# Peripherals.net
KiCad netlist of a schematic drawn in Altium Designer
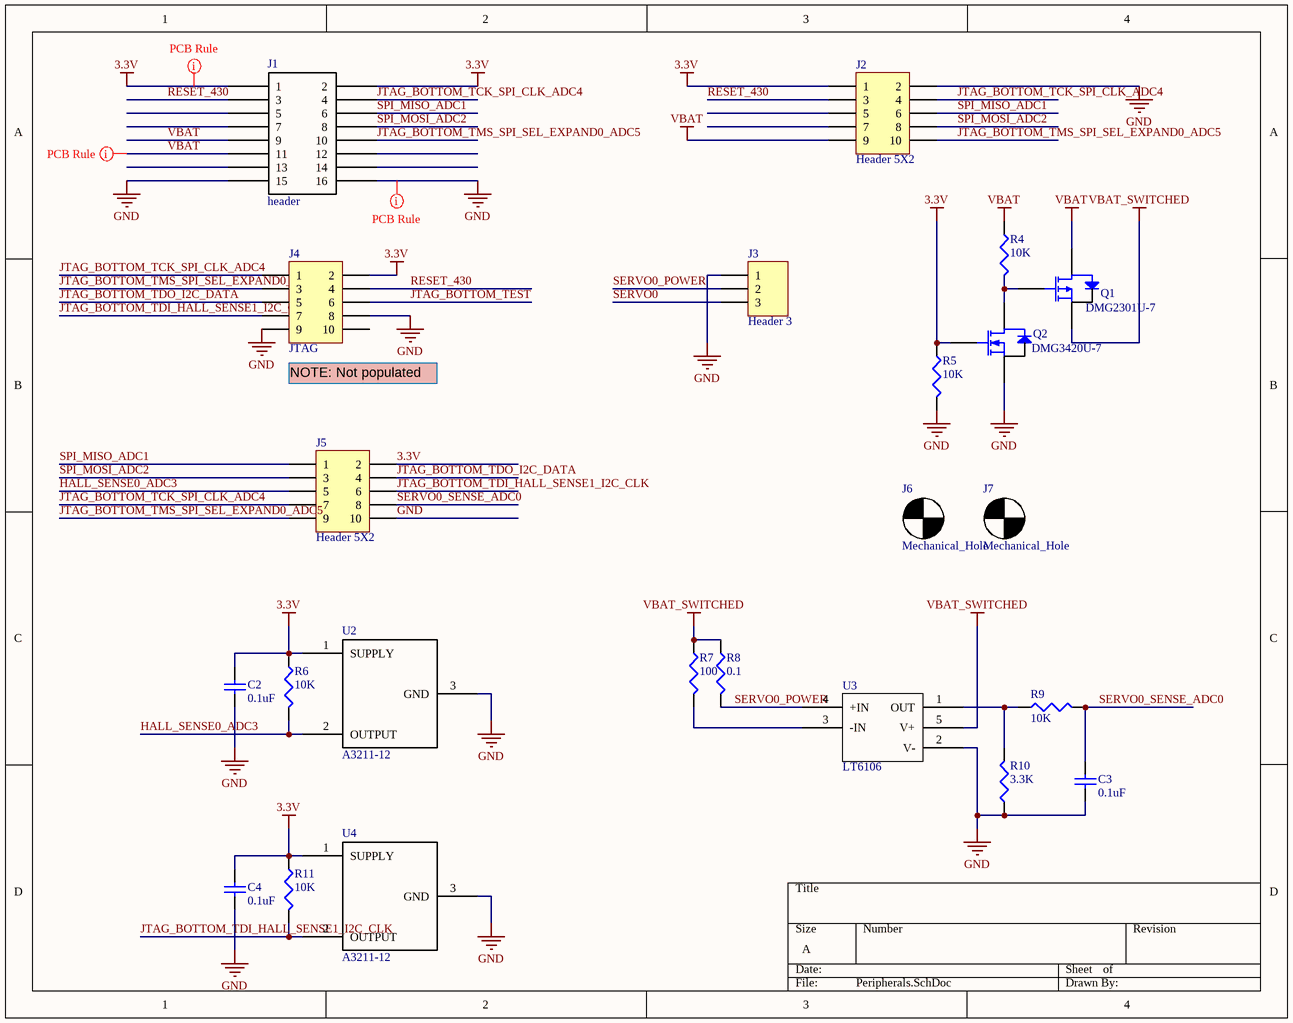
[diagram p0: Peripherals.SchDoc]

(export (version "E")
  (design (tool "Eeschema 10.0.6"))
  (components
    (comp (ref "C2")
      (value "0.1uF")
      (footprint "CAPC1005L")
      (description "Capacitor (Semiconductor SIM Model)")
      (fields (field (name "Comment") "Cap Semi") (field (name "PUBLISHER") "Altium Limited"))
      (libsource (lib "Miscellaneous Devices") (part "Cap Semi"))
    )
    (comp (ref "C3")
      (value "0.1uF")
      (footprint "CAPC1005L")
      (description "Capacitor (Semiconductor SIM Model)")
      (fields (field (name "Comment") "Cap Semi") (field (name "PUBLISHER") "Altium Limited"))
      (libsource (lib "Miscellaneous Devices") (part "Cap Semi"))
    )
    (comp (ref "C4")
      (value "0.1uF")
      (footprint "CAPC1005L")
      (description "Capacitor (Semiconductor SIM Model)")
      (fields (field (name "Comment") "Cap Semi") (field (name "PUBLISHER") "Altium Limited"))
      (libsource (lib "Miscellaneous Devices") (part "Cap Semi"))
    )
    (comp (ref "J1")
      (value "header")
      (footprint "HEADERSM 8X2")
      (libsource (lib "mrone") (part "HEADER 8X2"))
    )
    (comp (ref "J2")
      (value "Header 5X2")
      (footprint "HDR2X5")
      (description "Header, 5-Pin, Dual row")
      (fields (field (name "PUBLISHER") "Altium Limited"))
      (libsource (lib "mrone") (part "Header 5X2"))
    )
    (comp (ref "J3")
      (value "Header 3")
      (footprint "HDR1X3")
      (description "Header, 3-Pin")
      (fields (field (name "PUBLISHER") "Altium Limited"))
      (libsource (lib "mrone") (part "Header 3"))
    )
    (comp (ref "J4")
      (value "JTAG")
      (footprint "HDR2X5")
      (description "Header, 5-Pin, Dual row")
      (fields (field (name "PUBLISHER") "Altium Limited"))
      (libsource (lib "Miscellaneous Connectors") (part "Header 5X2"))
    )
    (comp (ref "J5")
      (value "Header 5X2")
      (footprint "HDR2X5")
      (description "Header, 5-Pin, Dual row")
      (fields (field (name "PUBLISHER") "Altium Limited"))
      (libsource (lib "mrone") (part "Header 5X2"))
    )
    (comp (ref "J6")
      (value "Mechanical_Hole")
      (footprint "#4_Screw_Hole")
      (description "A mechanical hole for mounting the board")
      (libsource (lib "mrone") (part "Mechanical_Hole"))
    )
    (comp (ref "J7")
      (value "Mechanical_Hole")
      (footprint "#4_Screw_Hole")
      (description "A mechanical hole for mounting the board")
      (libsource (lib "mrone") (part "Mechanical_Hole"))
    )
    (comp (ref "Q1") (value "DMG2301U-7") (footprint "SOT-23") (libsource (lib "mrone") (part "P-Mosfet")))
    (comp (ref "Q2") (value "DMG3420U-7") (footprint "SOT-23") (libsource (lib "mrone") (part "N-Mosfet")))
    (comp (ref "R4")
      (value "10K")
      (footprint "J1-0603")
      (description "Resistor")
      (fields (field (name "PUBLISHER") "Altium Limited"))
      (libsource (lib "Miscellaneous Devices") (part "Res3"))
    )
    (comp (ref "R5")
      (value "10K")
      (footprint "J1-0603")
      (description "Resistor")
      (fields (field (name "PUBLISHER") "Altium Limited"))
      (libsource (lib "Miscellaneous Devices") (part "Res3"))
    )
    (comp (ref "R6")
      (value "10K")
      (footprint "J1-0603")
      (description "Resistor")
      (fields (field (name "PUBLISHER") "Altium Limited"))
      (libsource (lib "Miscellaneous Devices") (part "Res3"))
    )
    (comp (ref "R7")
      (value "100")
      (footprint "J1-0603")
      (description "Resistor")
      (fields (field (name "Comment") "R_IN") (field (name "PUBLISHER") "Altium Limited"))
      (libsource (lib "Miscellaneous Devices") (part "Res3"))
    )
    (comp (ref "R8")
      (value "0.1")
      (footprint "J1-0603")
      (description "Resistor")
      (fields (field (name "Comment") "RLOAD") (field (name "PUBLISHER") "Altium Limited"))
      (libsource (lib "Miscellaneous Devices") (part "Res3"))
    )
    (comp (ref "R9")
      (value "10K")
      (footprint "J1-0603")
      (description "Resistor")
      (fields (field (name "Comment") "LPF") (field (name "PUBLISHER") "Altium Limited"))
      (libsource (lib "Miscellaneous Devices") (part "Res3"))
    )
    (comp (ref "R10")
      (value "3.3K")
      (footprint "J1-0603")
      (description "Resistor")
      (fields (field (name "Comment") "R_OUT") (field (name "PUBLISHER") "Altium Limited"))
      (libsource (lib "Miscellaneous Devices") (part "Res3"))
    )
    (comp (ref "R11")
      (value "10K")
      (footprint "J1-0603")
      (description "Resistor")
      (fields (field (name "PUBLISHER") "Altium Limited"))
      (libsource (lib "Miscellaneous Devices") (part "Res3"))
    )
    (comp (ref "U2")
      (value "A3211-12")
      (footprint "SOT-23 W")
      (description "Hall Effect Sensor")
      (libsource (lib "mrone") (part "A311-12"))
    )
    (comp (ref "U3")
      (value "LT6106")
      (footprint "TSOT-23-5_LT6106")
      (description "Current Sense Amplifier")
      (libsource (lib "mrone") (part "LT6106"))
    )
    (comp (ref "U4")
      (value "A3211-12")
      (footprint "SOT-23 W")
      (description "Hall Effect Sensor")
      (libsource (lib "mrone") (part "A311-12"))
    )
  )
  (nets
    (net (code "1") (name "/HALL_SENSE0_ADC3") (class "Default")
      (node (ref "J5") (pin "5") (pinfunction "5_5") (pintype "passive"))
      (node (ref "R6") (pin "2") (pinfunction "2_2") (pintype "passive"))
      (node (ref "U2") (pin "2") (pinfunction "OUTPUT_2") (pintype "passive"))
    )
    (net (code "2") (name "/JTAG_BOTTOM_TCK_SPI_CLK_ADC4") (class "Default")
      (node (ref "J1") (pin "4") (pinfunction "4_4") (pintype "passive"))
      (node (ref "J2") (pin "4") (pinfunction "4_4") (pintype "passive"))
      (node (ref "J4") (pin "1") (pinfunction "1_1") (pintype "passive"))
      (node (ref "J5") (pin "7") (pinfunction "7_7") (pintype "passive"))
    )
    (net (code "3") (name "/JTAG_BOTTOM_TDI_HALL_SENSE1_I2C_CLK") (class "Default")
      (node (ref "J4") (pin "7") (pinfunction "7_7") (pintype "passive"))
      (node (ref "J5") (pin "6") (pinfunction "6_6") (pintype "passive"))
      (node (ref "R11") (pin "2") (pinfunction "2_2") (pintype "passive"))
      (node (ref "U4") (pin "2") (pinfunction "OUTPUT_2") (pintype "passive"))
    )
    (net (code "4") (name "/JTAG_BOTTOM_TDO_I2C_DATA") (class "Default")
      (node (ref "J4") (pin "5") (pinfunction "5_5") (pintype "passive"))
      (node (ref "J5") (pin "4") (pinfunction "4_4") (pintype "passive"))
    )
    (net (code "5") (name "/JTAG_BOTTOM_TEST") (class "Default")
      (node (ref "J4") (pin "6") (pinfunction "6_6") (pintype "passive"))
    )
    (net (code "6") (name "/JTAG_BOTTOM_TMS_SPI_SEL_EXPAND0_ADC5") (class "Default")
      (node (ref "J1") (pin "10") (pinfunction "10_10") (pintype "passive"))
      (node (ref "J2") (pin "10") (pinfunction "10_10") (pintype "passive"))
      (node (ref "J4") (pin "3") (pinfunction "3_3") (pintype "passive"))
      (node (ref "J5") (pin "9") (pinfunction "9_9") (pintype "passive"))
    )
    (net (code "7") (name "/RESET_430") (class "Default")
      (node (ref "J1") (pin "3") (pinfunction "3_3") (pintype "passive"))
      (node (ref "J2") (pin "3") (pinfunction "3_3") (pintype "passive"))
      (node (ref "J4") (pin "4") (pinfunction "4_4") (pintype "passive"))
    )
    (net (code "8") (name "/SERVO0") (class "Default")
      (node (ref "J3") (pin "3") (pinfunction "3_3") (pintype "passive"))
    )
    (net (code "9") (name "/SERVO0_POWER") (class "Default")
      (node (ref "J3") (pin "2") (pinfunction "2_2") (pintype "passive"))
      (node (ref "R8") (pin "2") (pinfunction "2_2") (pintype "passive"))
      (node (ref "U3") (pin "4") (pinfunction "+IN_4") (pintype "passive"))
    )
    (net (code "10") (name "/SERVO0_SENSE_ADC0") (class "Default")
      (node (ref "C3") (pin "2") (pinfunction "2_2") (pintype "passive"))
      (node (ref "J5") (pin "8") (pinfunction "8_8") (pintype "passive"))
      (node (ref "R9") (pin "2") (pinfunction "2_2") (pintype "passive"))
    )
    (net (code "11") (name "/SPI_MISO_ADC1") (class "Default")
      (node (ref "J1") (pin "6") (pinfunction "6_6") (pintype "passive"))
      (node (ref "J2") (pin "6") (pinfunction "6_6") (pintype "passive"))
      (node (ref "J5") (pin "1") (pinfunction "1_1") (pintype "passive"))
    )
    (net (code "12") (name "/SPI_MOSI_ADC2") (class "Default")
      (node (ref "J1") (pin "8") (pinfunction "8_8") (pintype "passive"))
      (node (ref "J2") (pin "8") (pinfunction "8_8") (pintype "passive"))
      (node (ref "J5") (pin "3") (pinfunction "3_3") (pintype "passive"))
    )
    (net (code "13") (name "3.3V") (class "Default")
      (node (ref "C2") (pin "2") (pinfunction "2_2") (pintype "passive"))
      (node (ref "C4") (pin "2") (pinfunction "2_2") (pintype "passive"))
      (node (ref "J1") (pin "1") (pinfunction "1_1") (pintype "passive"))
      (node (ref "J1") (pin "2") (pinfunction "2_2") (pintype "passive"))
      (node (ref "J2") (pin "1") (pinfunction "1_1") (pintype "passive"))
      (node (ref "J4") (pin "2") (pinfunction "2_2") (pintype "passive"))
      (node (ref "J5") (pin "2") (pinfunction "2_2") (pintype "passive"))
      (node (ref "Q2") (pin "1") (pinfunction "G_1") (pintype "passive"))
      (node (ref "R11") (pin "1") (pinfunction "1_1") (pintype "passive"))
      (node (ref "R5") (pin "1") (pinfunction "1_1") (pintype "passive"))
      (node (ref "R6") (pin "1") (pinfunction "1_1") (pintype "passive"))
      (node (ref "U2") (pin "1") (pinfunction "SUPPLY_1") (pintype "passive"))
      (node (ref "U4") (pin "1") (pinfunction "SUPPLY_1") (pintype "passive"))
    )
    (net (code "14") (name "GND") (class "Default")
      (node (ref "C2") (pin "1") (pinfunction "1_1") (pintype "passive"))
      (node (ref "C3") (pin "1") (pinfunction "1_1") (pintype "passive"))
      (node (ref "C4") (pin "1") (pinfunction "1_1") (pintype "passive"))
      (node (ref "J1") (pin "15") (pinfunction "15_15") (pintype "passive"))
      (node (ref "J1") (pin "16") (pinfunction "16_16") (pintype "passive"))
      (node (ref "J2") (pin "2") (pinfunction "2_2") (pintype "passive"))
      (node (ref "J3") (pin "1") (pinfunction "1_1") (pintype "passive"))
      (node (ref "J4") (pin "8") (pinfunction "8_8") (pintype "passive"))
      (node (ref "J4") (pin "9") (pinfunction "9_9") (pintype "passive"))
      (node (ref "J5") (pin "10") (pinfunction "10_10") (pintype "passive"))
      (node (ref "Q2") (pin "2") (pinfunction "S_2") (pintype "passive"))
      (node (ref "R10") (pin "1") (pinfunction "1_1") (pintype "passive"))
      (node (ref "R5") (pin "2") (pinfunction "2_2") (pintype "passive"))
      (node (ref "U2") (pin "3") (pinfunction "GND_3") (pintype "passive"))
      (node (ref "U3") (pin "2") (pinfunction "V-_2") (pintype "passive"))
      (node (ref "U4") (pin "3") (pinfunction "GND_3") (pintype "passive"))
    )
    (net (code "15") (name "Net-(Q1-G)") (class "Default")
      (node (ref "Q1") (pin "1") (pinfunction "G_1") (pintype "passive"))
      (node (ref "Q2") (pin "3") (pinfunction "D_3") (pintype "passive"))
      (node (ref "R4") (pin "2") (pinfunction "2_2") (pintype "passive"))
    )
    (net (code "16") (name "Net-(U3--IN)") (class "Default")
      (node (ref "R7") (pin "2") (pinfunction "2_2") (pintype "passive"))
      (node (ref "U3") (pin "3") (pinfunction "-IN_3") (pintype "passive"))
    )
    (net (code "17") (name "Net-(U3-OUT)") (class "Default")
      (node (ref "R10") (pin "2") (pinfunction "2_2") (pintype "passive"))
      (node (ref "R9") (pin "1") (pinfunction "1_1") (pintype "passive"))
      (node (ref "U3") (pin "1") (pinfunction "OUT_1") (pintype "passive"))
    )
    (net (code "18") (name "VBAT") (class "Default")
      (node (ref "J1") (pin "11") (pinfunction "11_11") (pintype "passive"))
      (node (ref "J1") (pin "9") (pinfunction "9_9") (pintype "passive"))
      (node (ref "J2") (pin "9") (pinfunction "9_9") (pintype "passive"))
      (node (ref "Q1") (pin "3") (pinfunction "D_3") (pintype "passive"))
      (node (ref "R4") (pin "1") (pinfunction "1_1") (pintype "passive"))
    )
    (net (code "19") (name "VBAT_SWITCHED") (class "Default")
      (node (ref "Q1") (pin "2") (pinfunction "S_2") (pintype "passive"))
      (node (ref "R7") (pin "1") (pinfunction "1_1") (pintype "passive"))
      (node (ref "R8") (pin "1") (pinfunction "1_1") (pintype "passive"))
      (node (ref "U3") (pin "5") (pinfunction "V+_5") (pintype "passive"))
    )
    (net (code "20") (name "unconnected-(J1-Pad5)") (class "Default")
      (node (ref "J1") (pin "5") (pinfunction "5_5") (pintype "passive"))
    )
    (net (code "21") (name "unconnected-(J1-Pad7)") (class "Default")
      (node (ref "J1") (pin "7") (pinfunction "7_7") (pintype "passive"))
    )
    (net (code "22") (name "unconnected-(J1-Pad12)") (class "Default")
      (node (ref "J1") (pin "12") (pinfunction "12_12") (pintype "passive"))
    )
    (net (code "23") (name "unconnected-(J1-Pad13)") (class "Default")
      (node (ref "J1") (pin "13") (pinfunction "13_13") (pintype "passive"))
    )
    (net (code "24") (name "unconnected-(J1-Pad14)") (class "Default")
      (node (ref "J1") (pin "14") (pinfunction "14_14") (pintype "passive"))
    )
    (net (code "25") (name "unconnected-(J2-Pad5)") (class "Default")
      (node (ref "J2") (pin "5") (pinfunction "5_5") (pintype "passive"))
    )
    (net (code "26") (name "unconnected-(J2-Pad7)") (class "Default")
      (node (ref "J2") (pin "7") (pinfunction "7_7") (pintype "passive"))
    )
    (net (code "27") (name "unconnected-(J4-Pad10)") (class "Default")
      (node (ref "J4") (pin "10") (pinfunction "10_10") (pintype "passive"))
    )
  )
)
